# GH3020_PD_Board.net
KiCad netlist of a schematic drawn in Altium Designer
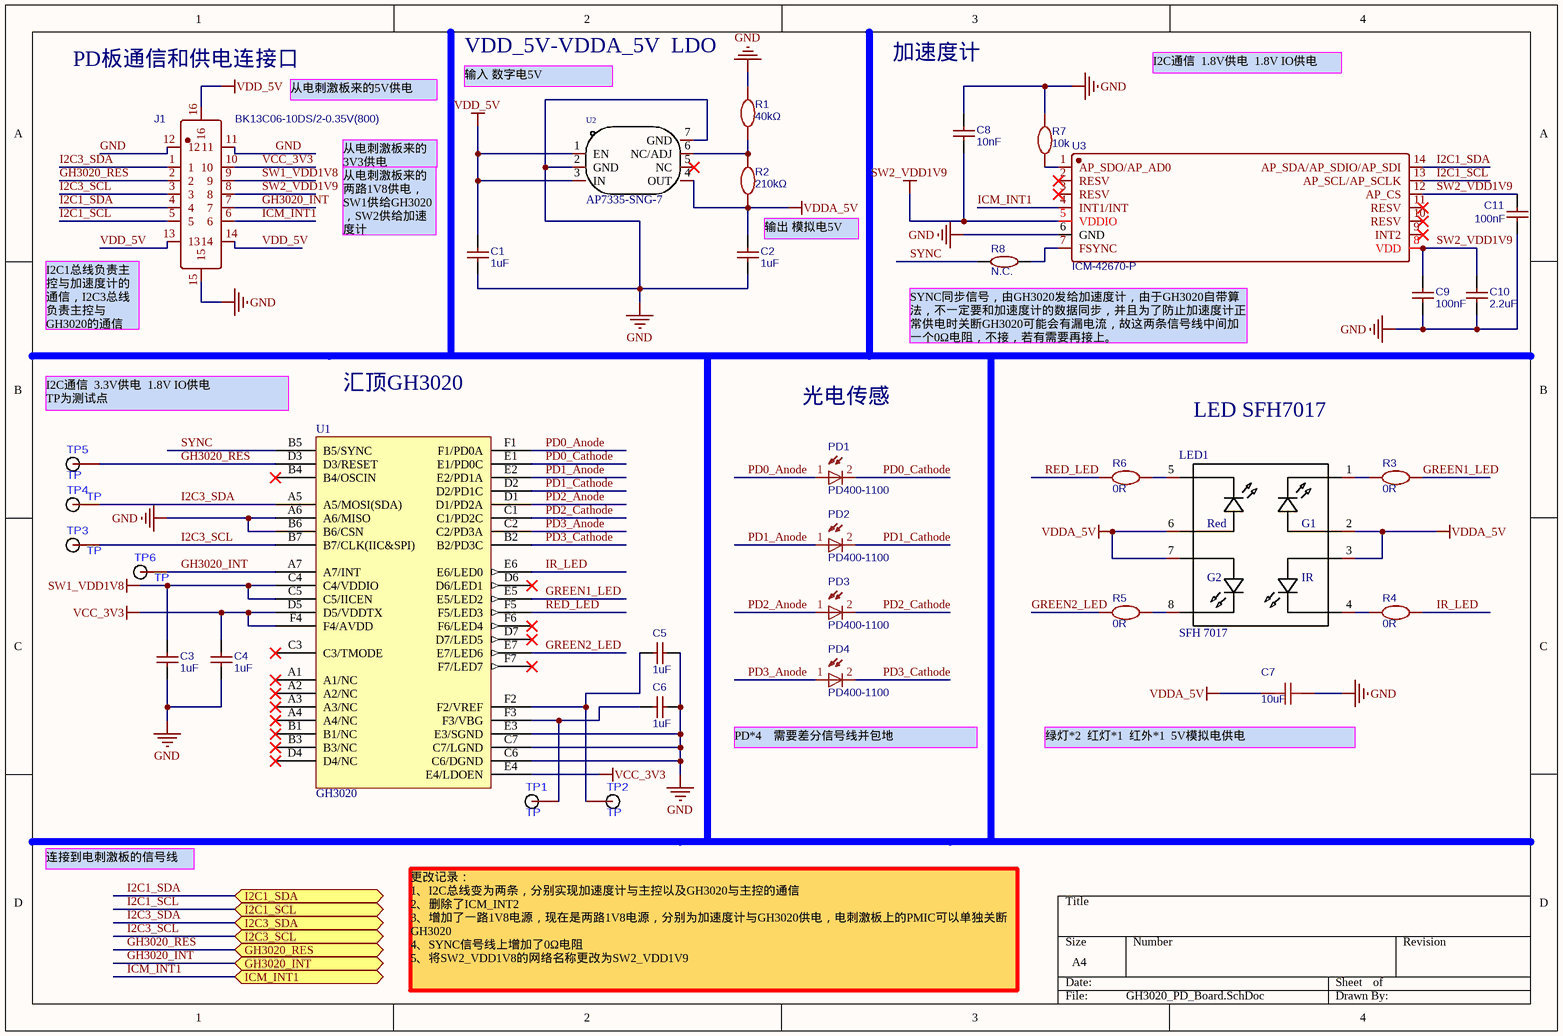
[diagram p0: GH3020_PD_Board.SchDoc]

(export (version "E")
  (design (tool "Eeschema 10.0.6"))
  (components
    (comp (ref "C1")
      (value "1uF")
      (footprint "C0201")
      (description "GRM033R61A105ME44D\r\n精度: ±20%\r\n额定电压: 10V\r\n材质(温度系数): X5R")
      (fields
        (field (name "BOM_MANUFACTURER PART") "CL10A105KB8NNNC")
        (field (name "BOM_SUPPLIER PART") "C15849")
      )
      (libsource (lib "smart bracelet") (part "1uF"))
    )
    (comp (ref "C2")
      (value "1uF")
      (footprint "C0201")
      (description "GRM033R61A105ME44D\r\n精度: ±20%\r\n额定电压: 10V\r\n材质(温度系数): X5R")
      (fields
        (field (name "BOM_MANUFACTURER PART") "CL10A105KB8NNNC")
        (field (name "BOM_SUPPLIER PART") "C15849")
      )
      (libsource (lib "smart bracelet") (part "1uF"))
    )
    (comp (ref "C3")
      (value "1uF")
      (footprint "C0201")
      (description "GRM033R61A105ME44D\r\n精度: ±20%\r\n额定电压: 10V\r\n材质(温度系数): X5R")
      (fields
        (field (name "BOM_MANUFACTURER PART") "CL10A105KB8NNNC")
        (field (name "BOM_SUPPLIER PART") "C15849")
      )
      (libsource (lib "smart bracelet") (part "1uF"))
    )
    (comp (ref "C4")
      (value "1uF")
      (footprint "C0201")
      (description "GRM033R61A105ME44D\r\n精度: ±20%\r\n额定电压: 10V\r\n材质(温度系数): X5R")
      (fields
        (field (name "BOM_MANUFACTURER PART") "CL10A105KB8NNNC")
        (field (name "BOM_SUPPLIER PART") "C15849")
      )
      (libsource (lib "smart bracelet") (part "1uF"))
    )
    (comp (ref "C5")
      (value "1uF")
      (footprint "C0201")
      (description "GRM033R61A105ME44D\r\n精度: ±20%\r\n额定电压: 10V\r\n材质(温度系数): X5R")
      (fields
        (field (name "BOM_MANUFACTURER PART") "CL10A105KB8NNNC")
        (field (name "BOM_SUPPLIER PART") "C15849")
      )
      (libsource (lib "smart bracelet") (part "1uF"))
    )
    (comp (ref "C6")
      (value "1uF")
      (footprint "C0201")
      (description "GRM033R61A105ME44D\r\n精度: ±20%\r\n额定电压: 10V\r\n材质(温度系数): X5R")
      (fields
        (field (name "BOM_MANUFACTURER PART") "CL10A105KB8NNNC")
        (field (name "BOM_SUPPLIER PART") "C15849")
      )
      (libsource (lib "smart bracelet") (part "1uF"))
    )
    (comp (ref "C7")
      (value "10uF")
      (footprint "C0603")
      (fields
        (field (name "BOM_SUPPLIER PART") "C913904")
        (field (name "BOM_MANUFACTURER PART") "CL10A225KB8NNNC")
        (field (name "CONTRIBUTOR") "LCSC")
      )
      (libsource (lib "Copy of smart bracelet") (part "C0603"))
    )
    (comp (ref "C8")
      (value "10nF")
      (footprint "C0201")
      (description "0201B103K250NT\r\n精度: ±10%\r\n额定电压: 25V\r\n材质(温度系数): X7R")
      (fields
        (field (name "BOM_MANUFACTURER PART") "CL10A105KB8NNNC")
        (field (name "BOM_SUPPLIER PART") "C15849")
      )
      (libsource (lib "smart bracelet") (part "1uF"))
    )
    (comp (ref "C9")
      (value "100nF")
      (footprint "C0201")
      (description "CL03A104KO3NNNC\r\n精度: ±10%\r\n额定电压: 16V\r\n材质(温度系数): X5R")
      (fields
        (field (name "BOM_MANUFACTURER PART") "CL10A105KB8NNNC")
        (field (name "BOM_SUPPLIER PART") "C15849")
      )
      (libsource (lib "smart bracelet") (part "1uF"))
    )
    (comp (ref "C10")
      (value "2.2uF")
      (footprint "C0201")
      (description "GRM033R61A225KE47D\r\n精度: ±10%\r\n额定电压: 10V\r\n材质(温度系数): X5R")
      (fields
        (field (name "BOM_MANUFACTURER PART") "CL10A105KB8NNNC")
        (field (name "BOM_SUPPLIER PART") "C15849")
      )
      (libsource (lib "smart bracelet") (part "1uF"))
    )
    (comp (ref "C11")
      (value "100nF")
      (footprint "C0201")
      (description "CL03A104KO3NNNC\r\n精度: ±10%\r\n额定电压: 16V\r\n材质(温度系数): X5R")
      (fields
        (field (name "BOM_MANUFACTURER PART") "CL10A105KB8NNNC")
        (field (name "BOM_SUPPLIER PART") "C15849")
      )
      (libsource (lib "smart bracelet") (part "1uF"))
    )
    (comp (ref "J1")
      (value "BK13C06-10DS/2-0.35V(800)")
      (footprint "Copy of smart bracelet:CONN-SMD_BK13C06-10DS-2-0.35V-800")
      (fields (field (name "MANUFACTURER") "HRS(广濑)") (field (name "CONTRIBUTOR") "lcsc"))
      (libsource (lib "Copy of smart bracelet") (part "10pin_ds_BK13C06-10DS/2-0.35V(800)"))
    )
    (comp (ref "LED1")
      (value "SFH 7017")
      (footprint "SFH7017")
      (libsource (lib "Copy of smart bracelet") (part "SFH 7017"))
    )
    (comp (ref "PD1")
      (value "PD400-1100")
      (footprint "SFH2703")
      (fields (field (name "CONTRIBUTOR") "Joshua312"))
      (libsource (lib "Copy of smart bracelet") (part "SFH2073"))
    )
    (comp (ref "PD2")
      (value "PD400-1100")
      (footprint "SFH2703")
      (fields (field (name "CONTRIBUTOR") "Joshua312"))
      (libsource (lib "Copy of smart bracelet") (part "SFH2073"))
    )
    (comp (ref "PD3")
      (value "PD400-1100")
      (footprint "SFH2703")
      (fields (field (name "CONTRIBUTOR") "Joshua312"))
      (libsource (lib "Copy of smart bracelet") (part "SFH2073"))
    )
    (comp (ref "PD4")
      (value "PD400-1100")
      (footprint "SFH2703")
      (fields (field (name "CONTRIBUTOR") "Joshua312"))
      (libsource (lib "Copy of smart bracelet") (part "SFH2073"))
    )
    (comp (ref "R1")
      (value "40kΩ")
      (footprint "0603R")
      (description "SCR0603F40K\r\n精度: ±1%\r\n功率: 100mW")
      (fields
        (field (name "BOM_SUPPLIER PART") "C413709")
        (field (name "BOM_MANUFACTURER PART") "ERJPB6B2003V")
        (field (name "CONTRIBUTOR") "LCSC")
      )
      (libsource (lib "smart bracelet") (part "200kΩ"))
    )
    (comp (ref "R2")
      (value "210kΩ")
      (footprint "0603R")
      (description "0603WAF2103T5E\r\n精度: ±1%\r\n功率: 100mW")
      (fields
        (field (name "BOM_SUPPLIER PART") "C413709")
        (field (name "BOM_MANUFACTURER PART") "ERJPB6B2003V")
        (field (name "CONTRIBUTOR") "LCSC")
      )
      (libsource (lib "smart bracelet") (part "200kΩ"))
    )
    (comp (ref "R3")
      (value "0R")
      (footprint "RES0201")
      (description "0201WMF0000TEE\r\n精度: ±1%\r\n功率: 50mW")
      (fields
        (field (name "BOM_SUPPLIER PART") "C2989113")
        (field (name "BOM_MANUFACTURER PART") "TC0325B1000T5F")
        (field (name "CONTRIBUTOR") "lcsc")
      )
      (libsource (lib "Copy of smart bracelet") (part "RES0201"))
    )
    (comp (ref "R4")
      (value "0R")
      (footprint "RES0201")
      (description "0201WMF0000TEE\r\n精度: ±1%\r\n功率: 50mW")
      (fields
        (field (name "BOM_SUPPLIER PART") "C2989113")
        (field (name "BOM_MANUFACTURER PART") "TC0325B1000T5F")
        (field (name "CONTRIBUTOR") "lcsc")
      )
      (libsource (lib "Copy of smart bracelet") (part "RES0201"))
    )
    (comp (ref "R5")
      (value "0R")
      (footprint "RES0201")
      (description "0201WMF0000TEE\r\n精度: ±1%\r\n功率: 50mW")
      (fields
        (field (name "BOM_SUPPLIER PART") "C2989113")
        (field (name "BOM_MANUFACTURER PART") "TC0325B1000T5F")
        (field (name "CONTRIBUTOR") "lcsc")
      )
      (libsource (lib "Copy of smart bracelet") (part "RES0201"))
    )
    (comp (ref "R6")
      (value "0R")
      (footprint "RES0201")
      (description "0201WMF0000TEE\r\n精度: ±1%\r\n功率: 50mW")
      (fields
        (field (name "BOM_SUPPLIER PART") "C2989113")
        (field (name "BOM_MANUFACTURER PART") "TC0325B1000T5F")
        (field (name "CONTRIBUTOR") "lcsc")
      )
      (libsource (lib "Copy of smart bracelet") (part "RES0201"))
    )
    (comp (ref "R7")
      (value "10k")
      (footprint "smart bracelet:RES0201")
      (description "0201WMF1002TEE\r\n精度: ±1%\r\n功率: 50mW")
      (fields
        (field (name "BOM_SUPPLIER PART") "C2989113")
        (field (name "BOM_MANUFACTURER PART") "TC0325B1000T5F")
        (field (name "CONTRIBUTOR") "lcsc")
      )
      (libsource (lib "smart bracelet") (part "RES0201"))
    )
    (comp (ref "R8")
      (value "N.C.")
      (footprint "Copy of smart bracelet:C0201")
      (description "0201WMF0000TEE\r\n精度: ±1%\r\n功率: 50mW")
      (fields
        (field (name "BOM_MANUFACTURER PART") "ERJ3GEY0R00V")
        (field (name "BOM_SUPPLIER PART") "C122704")
      )
      (libsource (lib "smart bracelet") (part "0Ω"))
    )
    (comp (ref "TP1")
      (value "TP")
      (footprint "Testpoint")
      (libsource (lib "Copy of smart bracelet") (part "TP"))
    )
    (comp (ref "TP2")
      (value "TP")
      (footprint "Testpoint")
      (libsource (lib "Copy of smart bracelet") (part "TP"))
    )
    (comp (ref "TP3")
      (value "TP")
      (footprint "Testpoint")
      (libsource (lib "Copy of smart bracelet") (part "TP"))
    )
    (comp (ref "TP4")
      (value "TP")
      (footprint "Testpoint")
      (libsource (lib "Copy of smart bracelet") (part "TP"))
    )
    (comp (ref "TP5")
      (value "TP")
      (footprint "Testpoint")
      (libsource (lib "Copy of smart bracelet") (part "TP"))
    )
    (comp (ref "TP6")
      (value "TP")
      (footprint "Testpoint")
      (libsource (lib "Copy of smart bracelet") (part "TP"))
    )
    (comp (ref "U1")
      (value "GH3020")
      (footprint "WLCSP42")
      (libsource (lib "Copy of smart bracelet") (part "GH3020"))
    )
    (comp (ref "U2")
      (value "AP7335-SNG-7")
      (footprint "U-DFN2020-6_L2.0-W2.0-P0.65-BL-EP")
      (fields
        (field (name "MANUFACTURER") "DIODES(美台)")
        (field (name "MANUFACTURER PART") "AP7335-18SNG-7")
        (field (name "NAME") "AP7335-SNG-7")
      )
      (libsource (lib "smart bracelet") (part "AP7335-18SNG-7"))
    )
    (comp (ref "U3")
      (value "ICM-42670-P")
      (footprint "Copy of smart bracelet:LGA-14_L3.0-W2.5-P0.50-TL_QMI8658A")
      (fields (field (name "MANUFACTURER") "TDK InvenSense(应美盛)") (field (name "CONTRIBUTOR") "lcsc"))
      (libsource (lib "smart bracelet") (part "ICM-42670-P"))
    )
  )
  (nets
    (net (code "1") (name "/GH3020_INT") (class "Default")
      (node (ref "J1") (pin "7") (pinfunction "7_7") (pintype "passive"))
      (node (ref "TP6") (pin "1") (pinfunction "text_1") (pintype "passive"))
      (node (ref "U1") (pin "A7") (pinfunction "A7/INT_A7") (pintype "passive"))
    )
    (net (code "2") (name "/GH3020_RES") (class "Default")
      (node (ref "J1") (pin "2") (pinfunction "2_2") (pintype "passive"))
      (node (ref "TP5") (pin "1") (pinfunction "text_1") (pintype "passive"))
      (node (ref "U1") (pin "D3") (pinfunction "D3/RESET_D3") (pintype "passive"))
    )
    (net (code "3") (name "/GREEN1_LED") (class "Default")
      (node (ref "R3") (pin "1") (pinfunction "1_1") (pintype "passive"))
      (node (ref "U1") (pin "E5") (pinfunction "E5/LED2_E5") (pintype "output"))
    )
    (net (code "4") (name "/GREEN2_LED") (class "Default")
      (node (ref "R5") (pin "2") (pinfunction "2_2") (pintype "passive"))
      (node (ref "U1") (pin "E7") (pinfunction "E7/LED6_E7") (pintype "output"))
    )
    (net (code "5") (name "/I2C1_SCL") (class "Default")
      (node (ref "J1") (pin "5") (pinfunction "5_5") (pintype "passive"))
      (node (ref "U3") (pin "13") (pinfunction "AP_SCL/AP_SCLK_13") (pintype "passive"))
    )
    (net (code "6") (name "/I2C1_SDA") (class "Default")
      (node (ref "J1") (pin "4") (pinfunction "4_4") (pintype "passive"))
      (node (ref "U3") (pin "14") (pinfunction "AP_SDA/AP_SDIO/AP_SDI_14") (pintype "passive"))
    )
    (net (code "7") (name "/I2C3_SCL") (class "Default")
      (node (ref "J1") (pin "3") (pinfunction "3_3") (pintype "passive"))
      (node (ref "TP3") (pin "1") (pinfunction "text_1") (pintype "passive"))
      (node (ref "U1") (pin "B7") (pinfunction "B7/CLK(IIC&SPI)_B7") (pintype "passive"))
    )
    (net (code "8") (name "/I2C3_SDA") (class "Default")
      (node (ref "J1") (pin "1") (pinfunction "1_1") (pintype "passive"))
      (node (ref "TP4") (pin "1") (pinfunction "text_1") (pintype "passive"))
      (node (ref "U1") (pin "A5") (pinfunction "A5/MOSI(SDA)_A5") (pintype "passive"))
    )
    (net (code "9") (name "/ICM_INT1") (class "Default")
      (node (ref "J1") (pin "6") (pinfunction "6_6") (pintype "passive"))
      (node (ref "U3") (pin "4") (pinfunction "INT1/INT_4") (pintype "passive"))
    )
    (net (code "10") (name "/IR_LED") (class "Default")
      (node (ref "R4") (pin "1") (pinfunction "1_1") (pintype "passive"))
      (node (ref "U1") (pin "E6") (pinfunction "E6/LED0_E6") (pintype "output"))
    )
    (net (code "11") (name "/PD0_Anode") (class "Default")
      (node (ref "PD1") (pin "1") (pinfunction "1_1") (pintype "passive"))
      (node (ref "U1") (pin "F1") (pinfunction "F1/PD0A_F1") (pintype "passive"))
    )
    (net (code "12") (name "/PD0_Cathode") (class "Default")
      (node (ref "PD1") (pin "2") (pinfunction "2_2") (pintype "passive"))
      (node (ref "U1") (pin "E1") (pinfunction "E1/PD0C_E1") (pintype "passive"))
    )
    (net (code "13") (name "/PD1_Anode") (class "Default")
      (node (ref "PD2") (pin "1") (pinfunction "1_1") (pintype "passive"))
      (node (ref "U1") (pin "E2") (pinfunction "E2/PD1A_E2") (pintype "passive"))
    )
    (net (code "14") (name "/PD1_Cathode") (class "Default")
      (node (ref "PD2") (pin "2") (pinfunction "2_2") (pintype "passive"))
      (node (ref "U1") (pin "D2") (pinfunction "D2/PD1C_D2") (pintype "passive"))
    )
    (net (code "15") (name "/PD2_Anode") (class "Default")
      (node (ref "PD3") (pin "1") (pinfunction "1_1") (pintype "passive"))
      (node (ref "U1") (pin "D1") (pinfunction "D1/PD2A_D1") (pintype "passive"))
    )
    (net (code "16") (name "/PD2_Cathode") (class "Default")
      (node (ref "PD3") (pin "2") (pinfunction "2_2") (pintype "passive"))
      (node (ref "U1") (pin "C1") (pinfunction "C1/PD2C_C1") (pintype "passive"))
    )
    (net (code "17") (name "/PD3_Anode") (class "Default")
      (node (ref "PD4") (pin "1") (pinfunction "1_1") (pintype "passive"))
      (node (ref "U1") (pin "C2") (pinfunction "C2/PD3A_C2") (pintype "passive"))
    )
    (net (code "18") (name "/PD3_Cathode") (class "Default")
      (node (ref "PD4") (pin "2") (pinfunction "2_2") (pintype "passive"))
      (node (ref "U1") (pin "B2") (pinfunction "B2/PD3C_B2") (pintype "passive"))
    )
    (net (code "19") (name "/RED_LED") (class "Default")
      (node (ref "R6") (pin "2") (pinfunction "2_2") (pintype "passive"))
      (node (ref "U1") (pin "F5") (pinfunction "F5/LED3_F5") (pintype "output"))
    )
    (net (code "20") (name "/SYNC") (class "Default")
      (node (ref "R8") (pin "2") (pinfunction "2_2") (pintype "passive"))
      (node (ref "U1") (pin "B5") (pinfunction "B5/SYNC_B5") (pintype "passive"))
    )
    (net (code "21") (name "GND") (class "Default")
      (node (ref "C1") (pin "2") (pinfunction "2_2") (pintype "passive"))
      (node (ref "C10") (pin "2") (pinfunction "2_2") (pintype "passive"))
      (node (ref "C11") (pin "2") (pinfunction "2_2") (pintype "passive"))
      (node (ref "C2") (pin "2") (pinfunction "2_2") (pintype "passive"))
      (node (ref "C3") (pin "2") (pinfunction "2_2") (pintype "passive"))
      (node (ref "C4") (pin "2") (pinfunction "2_2") (pintype "passive"))
      (node (ref "C5") (pin "2") (pinfunction "2_2") (pintype "passive"))
      (node (ref "C6") (pin "2") (pinfunction "2_2") (pintype "passive"))
      (node (ref "C7") (pin "1") (pinfunction "1_1") (pintype "passive"))
      (node (ref "C8") (pin "2") (pinfunction "2_2") (pintype "passive"))
      (node (ref "C9") (pin "1") (pinfunction "1_1") (pintype "passive"))
      (node (ref "J1") (pin "11") (pinfunction "11_11") (pintype "passive"))
      (node (ref "J1") (pin "12") (pinfunction "12_12") (pintype "passive"))
      (node (ref "J1") (pin "15") (pinfunction "15_15") (pintype "passive"))
      (node (ref "R1") (pin "2") (pinfunction "2_2") (pintype "passive"))
      (node (ref "R7") (pin "1") (pinfunction "1_1") (pintype "passive"))
      (node (ref "U1") (pin "A6") (pinfunction "A6/MISO_A6") (pintype "passive"))
      (node (ref "U1") (pin "B6") (pinfunction "B6/CSN_B6") (pintype "passive"))
      (node (ref "U1") (pin "C6") (pinfunction "C6/DGND_C6") (pintype "passive"))
      (node (ref "U1") (pin "C7") (pinfunction "C7/LGND_C7") (pintype "passive"))
      (node (ref "U1") (pin "E3") (pinfunction "E3/SGND_E3") (pintype "passive"))
      (node (ref "U2") (pin "2") (pinfunction "GND_2") (pintype "passive"))
      (node (ref "U2") (pin "7") (pinfunction "GND_7") (pintype "passive"))
      (node (ref "U3") (pin "6") (pinfunction "GND_6") (pintype "passive"))
    )
    (net (code "22") (name "Net-(LED1-K_IR)") (class "Default")
      (node (ref "LED1") (pin "8") (pinfunction "K_IR_8") (pintype "passive"))
      (node (ref "R5") (pin "1") (pinfunction "1_1") (pintype "passive"))
    )
    (net (code "23") (name "Net-(LED1-K_red-Pad1)") (class "Default")
      (node (ref "LED1") (pin "1") (pinfunction "K_red_1") (pintype "passive"))
      (node (ref "R3") (pin "2") (pinfunction "2_2") (pintype "passive"))
    )
    (net (code "24") (name "Net-(LED1-K_red-Pad4)") (class "Default")
      (node (ref "LED1") (pin "4") (pinfunction "K_red_4") (pintype "passive"))
      (node (ref "R4") (pin "2") (pinfunction "2_2") (pintype "passive"))
    )
    (net (code "25") (name "Net-(LED1-K_red-Pad5)") (class "Default")
      (node (ref "LED1") (pin "5") (pinfunction "K_red_5") (pintype "passive"))
      (node (ref "R6") (pin "1") (pinfunction "1_1") (pintype "passive"))
    )
    (net (code "26") (name "Net-(TP1-text)") (class "Default")
      (node (ref "C6") (pin "1") (pinfunction "1_1") (pintype "passive"))
      (node (ref "TP1") (pin "1") (pinfunction "text_1") (pintype "passive"))
      (node (ref "U1") (pin "F3") (pinfunction "F3/VBG_F3") (pintype "passive"))
    )
    (net (code "27") (name "Net-(TP2-text)") (class "Default")
      (node (ref "C5") (pin "1") (pinfunction "1_1") (pintype "passive"))
      (node (ref "TP2") (pin "1") (pinfunction "text_1") (pintype "passive"))
      (node (ref "U1") (pin "F2") (pinfunction "F2/VREF_F2") (pintype "passive"))
    )
    (net (code "28") (name "Net-(U2-NC{slash}ADJ)") (class "Default")
      (node (ref "R1") (pin "1") (pinfunction "1_1") (pintype "passive"))
      (node (ref "R2") (pin "2") (pinfunction "2_2") (pintype "passive"))
      (node (ref "U2") (pin "6") (pinfunction "NC/ADJ_6") (pintype "passive"))
    )
    (net (code "29") (name "Net-(U3-AP_SDO{slash}AP_AD0)") (class "Default")
      (node (ref "R7") (pin "2") (pinfunction "2_2") (pintype "passive"))
      (node (ref "U3") (pin "1") (pinfunction "AP_SDO/AP_AD0_1") (pintype "passive"))
    )
    (net (code "30") (name "Net-(U3-FSYNC)") (class "Default")
      (node (ref "R8") (pin "1") (pinfunction "1_1") (pintype "passive"))
      (node (ref "U3") (pin "7") (pinfunction "FSYNC_7") (pintype "passive"))
    )
    (net (code "31") (name "SW1_VDD1V8") (class "Default")
      (node (ref "C3") (pin "1") (pinfunction "1_1") (pintype "passive"))
      (node (ref "J1") (pin "9") (pinfunction "9_9") (pintype "passive"))
      (node (ref "U1") (pin "C4") (pinfunction "C4/VDDIO_C4") (pintype "passive"))
      (node (ref "U1") (pin "C5") (pinfunction "C5/IICEN_C5") (pintype "passive"))
    )
    (net (code "32") (name "SW2_VDD1V9") (class "Default")
      (node (ref "C10") (pin "1") (pinfunction "1_1") (pintype "passive"))
      (node (ref "C11") (pin "1") (pinfunction "1_1") (pintype "passive"))
      (node (ref "C8") (pin "1") (pinfunction "1_1") (pintype "passive"))
      (node (ref "C9") (pin "2") (pinfunction "2_2") (pintype "passive"))
      (node (ref "J1") (pin "8") (pinfunction "8_8") (pintype "passive"))
      (node (ref "U3") (pin "12") (pinfunction "AP_CS_12") (pintype "passive"))
      (node (ref "U3") (pin "5") (pinfunction "VDDIO_5") (pintype "passive"))
      (node (ref "U3") (pin "8") (pinfunction "VDD_8") (pintype "passive"))
    )
    (net (code "33") (name "VCC_3V3") (class "Default")
      (node (ref "C4") (pin "1") (pinfunction "1_1") (pintype "passive"))
      (node (ref "J1") (pin "10") (pinfunction "10_10") (pintype "passive"))
      (node (ref "U1") (pin "D5") (pinfunction "D5/VDDTX_D5") (pintype "passive"))
      (node (ref "U1") (pin "E4") (pinfunction "E4/LDOEN_E4") (pintype "passive"))
      (node (ref "U1") (pin "F4") (pinfunction "F4/AVDD_F4") (pintype "passive"))
    )
    (net (code "34") (name "VDDA_5V") (class "Default")
      (node (ref "C2") (pin "1") (pinfunction "1_1") (pintype "passive"))
      (node (ref "C7") (pin "2") (pinfunction "2_2") (pintype "passive"))
      (node (ref "LED1") (pin "2") (pinfunction "K_red_2") (pintype "passive"))
      (node (ref "LED1") (pin "3") (pinfunction "Anode_3") (pintype "passive"))
      (node (ref "LED1") (pin "6") (pinfunction "K_red_6") (pintype "passive"))
      (node (ref "LED1") (pin "7") (pinfunction "K_red_7") (pintype "passive"))
      (node (ref "R2") (pin "1") (pinfunction "1_1") (pintype "passive"))
      (node (ref "U2") (pin "4") (pinfunction "OUT_4") (pintype "passive"))
    )
    (net (code "35") (name "VDD_5V") (class "Default")
      (node (ref "C1") (pin "1") (pinfunction "1_1") (pintype "passive"))
      (node (ref "J1") (pin "13") (pinfunction "13_13") (pintype "passive"))
      (node (ref "J1") (pin "14") (pinfunction "14_14") (pintype "passive"))
      (node (ref "J1") (pin "16") (pinfunction "16_16") (pintype "passive"))
      (node (ref "U2") (pin "1") (pinfunction "EN_1") (pintype "passive"))
      (node (ref "U2") (pin "3") (pinfunction "IN_3") (pintype "passive"))
    )
    (net (code "36") (name "unconnected-(U1-A1{slash}NC-PadA1)") (class "Default")
      (node (ref "U1") (pin "A1") (pinfunction "A1/NC_A1") (pintype "passive+no_connect"))
    )
    (net (code "37") (name "unconnected-(U1-A2{slash}NC-PadA2)") (class "Default")
      (node (ref "U1") (pin "A2") (pinfunction "A2/NC_A2") (pintype "passive+no_connect"))
    )
    (net (code "38") (name "unconnected-(U1-A3{slash}NC-PadA3)") (class "Default")
      (node (ref "U1") (pin "A3") (pinfunction "A3/NC_A3") (pintype "passive+no_connect"))
    )
    (net (code "39") (name "unconnected-(U1-A4{slash}NC-PadA4)") (class "Default")
      (node (ref "U1") (pin "A4") (pinfunction "A4/NC_A4") (pintype "passive+no_connect"))
    )
    (net (code "40") (name "unconnected-(U1-B1{slash}NC-PadB1)") (class "Default")
      (node (ref "U1") (pin "B1") (pinfunction "B1/NC_B1") (pintype "passive+no_connect"))
    )
    (net (code "41") (name "unconnected-(U1-B3{slash}NC-PadB3)") (class "Default")
      (node (ref "U1") (pin "B3") (pinfunction "B3/NC_B3") (pintype "passive+no_connect"))
    )
    (net (code "42") (name "unconnected-(U1-B4{slash}OSCIN-PadB4)") (class "Default")
      (node (ref "U1") (pin "B4") (pinfunction "B4/OSCIN_B4") (pintype "passive+no_connect"))
    )
    (net (code "43") (name "unconnected-(U1-C3{slash}TMODE-PadC3)") (class "Default")
      (node (ref "U1") (pin "C3") (pinfunction "C3/TMODE_C3") (pintype "passive+no_connect"))
    )
    (net (code "44") (name "unconnected-(U1-D4{slash}NC-PadD4)") (class "Default")
      (node (ref "U1") (pin "D4") (pinfunction "D4/NC_D4") (pintype "passive+no_connect"))
    )
    (net (code "45") (name "unconnected-(U1-D6{slash}LED1-PadD6)") (class "Default")
      (node (ref "U1") (pin "D6") (pinfunction "D6/LED1_D6") (pintype "output+no_connect"))
    )
    (net (code "46") (name "unconnected-(U1-D7{slash}LED5-PadD7)") (class "Default")
      (node (ref "U1") (pin "D7") (pinfunction "D7/LED5_D7") (pintype "output+no_connect"))
    )
    (net (code "47") (name "unconnected-(U1-F6{slash}LED4-PadF6)") (class "Default")
      (node (ref "U1") (pin "F6") (pinfunction "F6/LED4_F6") (pintype "output+no_connect"))
    )
    (net (code "48") (name "unconnected-(U1-F7{slash}LED7-PadF7)") (class "Default")
      (node (ref "U1") (pin "F7") (pinfunction "F7/LED7_F7") (pintype "output+no_connect"))
    )
    (net (code "49") (name "unconnected-(U2-NC-Pad5)") (class "Default")
      (node (ref "U2") (pin "5") (pinfunction "NC_5") (pintype "passive+no_connect"))
    )
    (net (code "50") (name "unconnected-(U3-INT2-Pad9)") (class "Default")
      (node (ref "U3") (pin "9") (pinfunction "INT2_9") (pintype "passive+no_connect"))
    )
    (net (code "51") (name "unconnected-(U3-RESV-Pad2)") (class "Default")
      (node (ref "U3") (pin "2") (pinfunction "RESV_2") (pintype "passive+no_connect"))
    )
    (net (code "52") (name "unconnected-(U3-RESV-Pad3)") (class "Default")
      (node (ref "U3") (pin "3") (pinfunction "RESV_3") (pintype "passive+no_connect"))
    )
    (net (code "53") (name "unconnected-(U3-RESV-Pad10)") (class "Default")
      (node (ref "U3") (pin "10") (pinfunction "RESV_10") (pintype "passive+no_connect"))
    )
    (net (code "54") (name "unconnected-(U3-RESV-Pad11)") (class "Default")
      (node (ref "U3") (pin "11") (pinfunction "RESV_11") (pintype "passive+no_connect"))
    )
  )
)
